# DB10025_Toplevel.net
KiCad netlist of a schematic drawn in Altium Designer
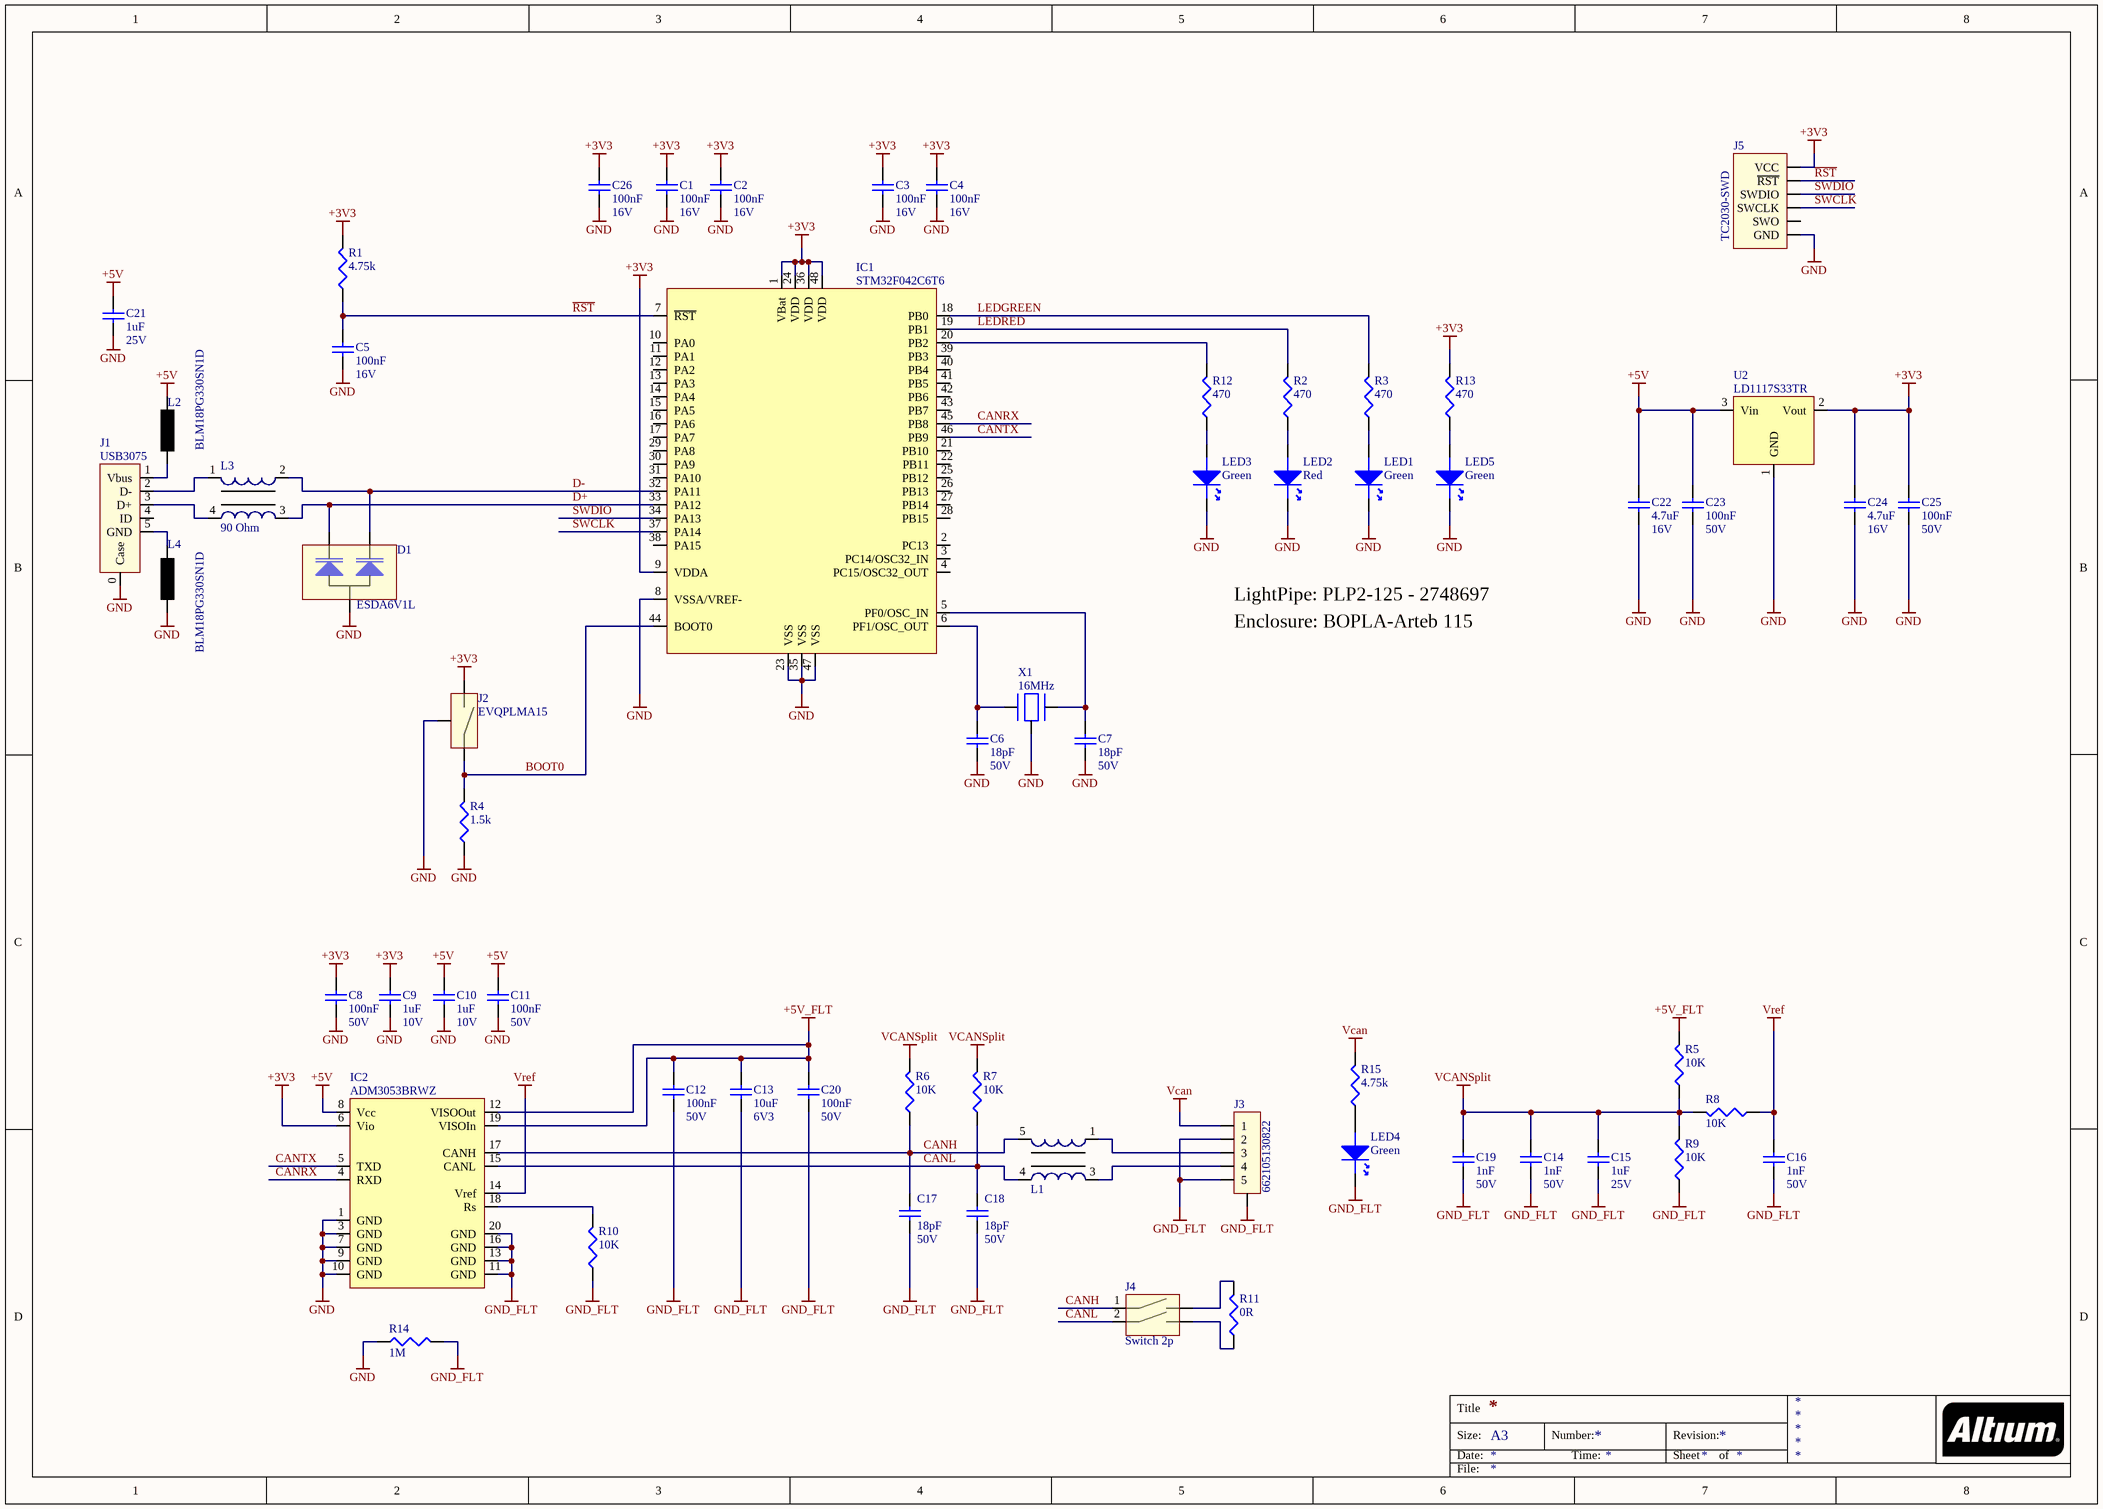
[diagram p0: DB10025_Toplevel.SchDoc]

(export (version "E")
  (design (tool "Eeschema 10.0.6"))
  (components
    (comp (ref "C1")
      (value "100nF")
      (footprint "C0402")
      (description "Capacitor, 100nF, 16V, X7R")
      (fields (field (name "VOLTAGE RATING") "16V"))
      (libsource (lib "AR_Capacitors_Ceramic") (part "100nF/0402/CER/16V"))
    )
    (comp (ref "C2")
      (value "100nF")
      (footprint "C0402")
      (description "Capacitor, 100nF, 16V, X7R")
      (fields (field (name "VOLTAGE RATING") "16V"))
      (libsource (lib "AR_Capacitors_Ceramic") (part "100nF/0402/CER/16V"))
    )
    (comp (ref "C3")
      (value "100nF")
      (footprint "C0402")
      (description "Capacitor, 100nF, 16V, X7R")
      (fields (field (name "VOLTAGE RATING") "16V"))
      (libsource (lib "AR_Capacitors_Ceramic") (part "100nF/0402/CER/16V"))
    )
    (comp (ref "C4")
      (value "100nF")
      (footprint "C0402")
      (description "Capacitor, 100nF, 16V, X7R")
      (fields (field (name "VOLTAGE RATING") "16V"))
      (libsource (lib "AR_Capacitors_Ceramic") (part "100nF/0402/CER/16V"))
    )
    (comp (ref "C5")
      (value "100nF")
      (footprint "C0402")
      (description "Capacitor, 100nF, 16V, X7R")
      (fields (field (name "VOLTAGE RATING") "16V"))
      (libsource (lib "AR_Capacitors_Ceramic") (part "100nF/0402/CER/16V"))
    )
    (comp (ref "C6")
      (value "18pF")
      (footprint "C0402")
      (description "Capacitor, 18pF, 50V, NP0")
      (fields (field (name "VOLTAGE RATING") "50V"))
      (libsource (lib "AR_Capacitors_Ceramic") (part "18pF/0402/CER/50V"))
    )
    (comp (ref "C7")
      (value "18pF")
      (footprint "C0402")
      (description "Capacitor, 18pF, 50V, NP0")
      (fields (field (name "VOLTAGE RATING") "50V"))
      (libsource (lib "AR_Capacitors_Ceramic") (part "18pF/0402/CER/50V"))
    )
    (comp (ref "C8")
      (value "100nF")
      (footprint "C0603")
      (description "Capacitor, 100nF, 50V, X7R")
      (fields (field (name "VOLTAGE RATING") "50V"))
      (libsource (lib "AR_Capacitors_Ceramic") (part "100nF/0603/CER/50V"))
    )
    (comp (ref "C9")
      (value "1uF")
      (footprint "C0603")
      (description "Capacitor, 1uF, 10V, X5R")
      (fields (field (name "VOLTAGE RATING") "10V"))
      (libsource (lib "AR_Capacitors_Ceramic") (part "1uF/0603/CER/10V/X5R"))
    )
    (comp (ref "C10")
      (value "1uF")
      (footprint "C0603")
      (description "Capacitor, 1uF, 10V, X5R")
      (fields (field (name "VOLTAGE RATING") "10V"))
      (libsource (lib "AR_Capacitors_Ceramic") (part "1uF/0603/CER/10V/X5R"))
    )
    (comp (ref "C11")
      (value "100nF")
      (footprint "C0603")
      (description "Capacitor, 100nF, 50V, X7R")
      (fields (field (name "VOLTAGE RATING") "50V"))
      (libsource (lib "AR_Capacitors_Ceramic") (part "100nF/0603/CER/50V"))
    )
    (comp (ref "C12")
      (value "100nF")
      (footprint "C0603")
      (description "Capacitor, 100nF, 50V, X7R")
      (fields (field (name "VOLTAGE RATING") "50V"))
      (libsource (lib "AR_Capacitors_Ceramic") (part "100nF/0603/CER/50V"))
    )
    (comp (ref "C13")
      (value "10uF")
      (footprint "C0603")
      (description "Capacitor, 10uF, 6.3V, X5R")
      (fields (field (name "VOLTAGE RATING") "6V3"))
      (libsource (lib "AR_Capacitors_Ceramic") (part "10uF/0603/CER/6V3/X5R"))
    )
    (comp (ref "C14")
      (value "1nF")
      (footprint "C0603")
      (description "Capacitor, 1nF, 50V, X7R")
      (fields (field (name "VOLTAGE RATING") "50V"))
      (libsource (lib "AR_Capacitors_Ceramic") (part "1nF/0603/CER/50V"))
    )
    (comp (ref "C15")
      (value "1uF")
      (footprint "C0603")
      (description "Capacitor, 1uF, 25V, X7R")
      (fields (field (name "VOLTAGE RATING") "25V"))
      (libsource (lib "AR_Capacitors_Ceramic") (part "1uF/0603/CER/25V"))
    )
    (comp (ref "C16")
      (value "1nF")
      (footprint "C0603")
      (description "Capacitor, 1nF, 50V, X7R")
      (fields (field (name "VOLTAGE RATING") "50V"))
      (libsource (lib "AR_Capacitors_Ceramic") (part "1nF/0603/CER/50V"))
    )
    (comp (ref "C17")
      (value "18pF")
      (footprint "C0603")
      (description "Capacitor, 18pF, 50V, C0G / NP0")
      (fields (field (name "VOLTAGE RATING") "50V"))
      (libsource (lib "AR_Capacitors_Ceramic") (part "18pF/0603/CER/50V"))
    )
    (comp (ref "C18")
      (value "18pF")
      (footprint "C0603")
      (description "Capacitor, 18pF, 50V, C0G / NP0")
      (fields (field (name "VOLTAGE RATING") "50V"))
      (libsource (lib "AR_Capacitors_Ceramic") (part "18pF/0603/CER/50V"))
    )
    (comp (ref "C19")
      (value "1nF")
      (footprint "C0603")
      (description "Capacitor, 1nF, 50V, X7R")
      (fields (field (name "VOLTAGE RATING") "50V"))
      (libsource (lib "AR_Capacitors_Ceramic") (part "1nF/0603/CER/50V"))
    )
    (comp (ref "C20")
      (value "100nF")
      (footprint "C0603")
      (description "Capacitor, 100nF, 50V, X7R")
      (fields (field (name "VOLTAGE RATING") "50V"))
      (libsource (lib "AR_Capacitors_Ceramic") (part "100nF/0603/CER/50V"))
    )
    (comp (ref "C21")
      (value "1uF")
      (footprint "C0603")
      (description "Capacitor, 1uF, 25V, X7R")
      (fields (field (name "VOLTAGE RATING") "25V"))
      (libsource (lib "AR_Capacitors_Ceramic") (part "1uF/0603/CER/25V"))
    )
    (comp (ref "C22")
      (value "4.7uF")
      (footprint "C-0805")
      (description "Capacitor, 4.7uF, 16V, X7R")
      (fields (field (name "VOLTAGE RATING") "16V"))
      (libsource (lib "AR_Capacitors_Ceramic") (part "4.7uF/0805/CER/16V"))
    )
    (comp (ref "C23")
      (value "100nF")
      (footprint "C-0805")
      (description "Capacitor, 100nF, 50V,  X7R")
      (fields (field (name "VOLTAGE RATING") "50V"))
      (libsource (lib "AR_Capacitors_Ceramic") (part "100nF/0805/CER/50V"))
    )
    (comp (ref "C24")
      (value "4.7uF")
      (footprint "C-0805")
      (description "Capacitor, 4.7uF, 16V, X7R")
      (fields (field (name "VOLTAGE RATING") "16V"))
      (libsource (lib "AR_Capacitors_Ceramic") (part "4.7uF/0805/CER/16V"))
    )
    (comp (ref "C25")
      (value "100nF")
      (footprint "C-0805")
      (description "Capacitor, 100nF, 50V,  X7R")
      (fields (field (name "VOLTAGE RATING") "50V"))
      (libsource (lib "AR_Capacitors_Ceramic") (part "100nF/0805/CER/50V"))
    )
    (comp (ref "C26")
      (value "100nF")
      (footprint "C0402")
      (description "Capacitor, 100nF, 16V, X7R")
      (fields (field (name "VOLTAGE RATING") "16V"))
      (libsource (lib "AR_Capacitors_Ceramic") (part "100nF/0402/CER/16V"))
    )
    (comp (ref "D1")
      (value "ESDA6V1L")
      (footprint "SOT23")
      (description "Diode TVS Dual, Vrwm: 5.25V, Vbr: 7.2V, Vc: 12.45V, Ippm: 15A")
      (libsource (lib "AR_Diodes") (part "ESDA6V1L"))
    )
    (comp (ref "IC1")
      (value "STM32F042C6T6")
      (footprint "LQFP48")
      (description "MCU, 32BIT CORTEX-M3, 72MHz")
      (libsource (lib "AR_Microcontrollers") (part "STM32F042C6T6"))
    )
    (comp (ref "IC2")
      (value "ADM3053BRWZ")
      (footprint "SOIC20")
      (description "CAN Transceiver isolated")
      (libsource (lib "AR_ICs") (part "ADM3053BRWZ"))
    )
    (comp (ref "J1")
      (value "USB3075")
      (footprint "USB3075")
      (description "USB 2.0 MICRO B, RCPT, 5POS, SMT")
      (libsource (lib "AR_Connectors") (part "USB3075"))
    )
    (comp (ref "J2")
      (value "EVQPLMA15")
      (footprint "EVQPLM")
      (description "SWITCH, TACT, 4.9MM, SMD, 2.6N")
      (libsource (lib "AR_Misc") (part "EVQPLMA15"))
    )
    (comp (ref "J3")
      (value "662105130822")
      (footprint "662105130822")
      (description "WR-MPC3 Series, 5Pin, Right Angle")
      (libsource (lib "AR_Connectors") (part "662105130822"))
    )
    (comp (ref "J4")
      (value "Switch 2p")
      (footprint "MCEMR-02")
      (description "SWITCH, DIL, SMD, 2WAY, SPST")
      (libsource (lib "AR_Misc") (part "WE-418121160802"))
    )
    (comp (ref "J5")
      (value "TC2030-SWD")
      (footprint "TC2030-IDC-NL")
      (description "TagConnect 2030")
      (libsource (lib "AR_Connectors") (part "TC2030-SWD"))
    )
    (comp (ref "L1")
      (value "CAN filter")
      (footprint "WE-SL1")
      (description "Common mode CAN filter")
      (libsource (lib "AR_Misc") (part "744212510"))
    )
    (comp (ref "L2")
      (value "BLM18PG330SN1D")
      (footprint "L0603")
      (description "Ferrite Bead, Impedance:33ohm, DC Resistance Max:0.025ohm, DC Current Rating:3A")
      (libsource (lib "AR_Inductors") (part "BLM18PG330SN1D"))
    )
    (comp (ref "L3")
      (value "90 Ohm")
      (footprint "WE-CNSW, 1206")
      (description "SMD Common Mode Noise Suppressor WE-CNSW,  Z= 90 Ohm")
      (fields
        (field (name "PARTNO") "744232090")
        (field (name "MANUFACTURER") "Würth Elektronik eiSos GmbH")
        (field (name "CREATED BY") "Christin Zierenner")
      )
      (libsource (lib "AR_Misc") (part "WE-CNSW 1206, 744232090"))
    )
    (comp (ref "L4")
      (value "BLM18PG330SN1D")
      (footprint "L0603")
      (description "Ferrite Bead, Impedance:33ohm, DC Resistance Max:0.025ohm, DC Current Rating:3A")
      (libsource (lib "AR_Inductors") (part "BLM18PG330SN1D"))
    )
    (comp (ref "LED1")
      (value "Green")
      (footprint "WL-SMSW_1204")
      (description "1204 LED Green Side")
      (libsource (lib "AR_LEDs") (part "155124GS73200"))
    )
    (comp (ref "LED2")
      (value "Red")
      (footprint "WL-SMSW_1204")
      (description "1204 LED Red Side")
      (libsource (lib "AR_LEDs") (part "155124RS73200"))
    )
    (comp (ref "LED3")
      (value "Green")
      (footprint "D-0805")
      (description "Led, Yellowish Green, Li:16mcd, Vf:2.2V, If:0.025A")
      (libsource (lib "AR_Misc") (part "SML-210MTT86N"))
    )
    (comp (ref "LED4")
      (value "Green")
      (footprint "WL-SMSW_1204")
      (description "1204 LED Green Side")
      (libsource (lib "AR_LEDs") (part "155124GS73200"))
    )
    (comp (ref "LED5")
      (value "Green")
      (footprint "D-0805")
      (description "Led, Yellowish Green, Li:16mcd, Vf:2.2V, If:0.025A")
      (libsource (lib "AR_Misc") (part "SML-210MTT86N"))
    )
    (comp (ref "R1")
      (value "4.75k")
      (footprint "0402")
      (description "Resistor, 4.75k, 0.1%, 0.0625W, 50V, 100PPM, 0402")
      (libsource (lib "AR_Resistors_SMD") (part "4.75k/0402/0063W/50V"))
    )
    (comp (ref "R2")
      (value "470")
      (footprint "0402")
      (description "Resistor, 470, 1%, 0.0625W, 50V, 100PPM, 0402")
      (libsource (lib "AR_Resistors_SMD") (part "470/0402/0063W/50V"))
    )
    (comp (ref "R3")
      (value "470")
      (footprint "0402")
      (description "Resistor, 470, 1%, 0.0625W, 50V, 100PPM, 0402")
      (libsource (lib "AR_Resistors_SMD") (part "470/0402/0063W/50V"))
    )
    (comp (ref "R4")
      (value "1.5k")
      (footprint "0402")
      (description "Resistor, 1.5k, 0.1%, 0.0625W, 50V, 100PPM, 0402")
      (libsource (lib "AR_Resistors_SMD") (part "1.5k/0402/0063W/50V"))
    )
    (comp (ref "R5")
      (value "10K")
      (footprint "0603")
      (description "Resistor, 10K, 1%, 0.063W, 50V, 100PPM, 0603")
      (libsource (lib "AR_Resistors_SMD") (part "10K/0603/0063W/50V"))
    )
    (comp (ref "R6")
      (value "10K")
      (footprint "0603")
      (description "Resistor, 10K, 1%, 0.063W, 50V, 100PPM, 0603")
      (libsource (lib "AR_Resistors_SMD") (part "10K/0603/0063W/50V"))
    )
    (comp (ref "R7")
      (value "10K")
      (footprint "0603")
      (description "Resistor, 10K, 1%, 0.063W, 50V, 100PPM, 0603")
      (libsource (lib "AR_Resistors_SMD") (part "10K/0603/0063W/50V"))
    )
    (comp (ref "R8")
      (value "10K")
      (footprint "0603")
      (description "Resistor, 10K, 1%, 0.063W, 50V, 100PPM, 0603")
      (libsource (lib "AR_Resistors_SMD") (part "10K/0603/0063W/50V"))
    )
    (comp (ref "R9")
      (value "10K")
      (footprint "0603")
      (description "Resistor, 10K, 1%, 0.063W, 50V, 100PPM, 0603")
      (libsource (lib "AR_Resistors_SMD") (part "10K/0603/0063W/50V"))
    )
    (comp (ref "R10")
      (value "10K")
      (footprint "0603")
      (description "Resistor, 10K, 1%, 0.063W, 50V, 100PPM, 0603")
      (libsource (lib "AR_Resistors_SMD") (part "10K/0603/0063W/50V"))
    )
    (comp (ref "R11")
      (value "0R")
      (footprint "0805")
      (description "Resistor, 0R, 0.1%, 0.1W, 150V, 200PPM, 0805")
      (libsource (lib "AR_Resistors_SMD") (part "0/0805/0100W/150V"))
    )
    (comp (ref "R12")
      (value "470")
      (footprint "0402")
      (description "Resistor, 470, 1%, 0.0625W, 50V, 100PPM, 0402")
      (libsource (lib "AR_Resistors_SMD") (part "470/0402/0063W/50V"))
    )
    (comp (ref "R13")
      (value "470")
      (footprint "0402")
      (description "Resistor, 470, 1%, 0.0625W, 50V, 100PPM, 0402")
      (libsource (lib "AR_Resistors_SMD") (part "470/0402/0063W/50V"))
    )
    (comp (ref "R14")
      (value "1M")
      (footprint "1206")
      (description "Resistor, 1M, 1%, 0.25W, 1kV, 200PPM, 1206")
      (libsource (lib "AR_Resistors_SMD") (part "1M/1206/0300W/1kV"))
    )
    (comp (ref "R15")
      (value "4.75k")
      (footprint "0402")
      (description "Resistor, 4.75k, 0.1%, 0.0625W, 50V, 100PPM, 0402")
      (libsource (lib "AR_Resistors_SMD") (part "4.75k/0402/0063W/50V"))
    )
    (comp (ref "U2")
      (value "LD1117S33TR")
      (footprint "SOT223")
      (description "LD1117S33TR - 3.3V LDO, REG, 0.8A, SOT223")
      (libsource (lib "AR_Vreg") (part "LD1117S33TR"))
    )
    (comp (ref "X1")
      (value "16MHz")
      (footprint "7M")
      (description "CRYSTAL, 16MHz,18PF CL, 3.2X2.5MM SMT")
      (libsource (lib "AR_Crystals") (part "7M-16.000MAAJ-T"))
    )
  )
  (nets
    (net (code "1") (name "+3V3") (class "Default")
      (node (ref "C1") (pin "2") (pinfunction "2_2") (pintype "passive"))
      (node (ref "C2") (pin "2") (pinfunction "2_2") (pintype "passive"))
      (node (ref "C24") (pin "2") (pinfunction "2_2") (pintype "passive"))
      (node (ref "C25") (pin "2") (pinfunction "2_2") (pintype "passive"))
      (node (ref "C26") (pin "2") (pinfunction "2_2") (pintype "passive"))
      (node (ref "C3") (pin "2") (pinfunction "2_2") (pintype "passive"))
      (node (ref "C4") (pin "2") (pinfunction "2_2") (pintype "passive"))
      (node (ref "C8") (pin "2") (pinfunction "2_2") (pintype "passive"))
      (node (ref "C9") (pin "2") (pinfunction "2_2") (pintype "passive"))
      (node (ref "IC1") (pin "1") (pinfunction "VBat_1") (pintype "passive"))
      (node (ref "IC1") (pin "24") (pinfunction "VDD_24") (pintype "passive"))
      (node (ref "IC1") (pin "36") (pinfunction "VDD_36") (pintype "passive"))
      (node (ref "IC1") (pin "48") (pinfunction "VDD_48") (pintype "passive"))
      (node (ref "IC1") (pin "9") (pinfunction "VDDA_9") (pintype "passive"))
      (node (ref "IC2") (pin "6") (pinfunction "Vio_6") (pintype "passive"))
      (node (ref "J2") (pin "2") (pinfunction "2_2") (pintype "passive"))
      (node (ref "J5") (pin "1") (pinfunction "VCC_1") (pintype "passive"))
      (node (ref "R1") (pin "2") (pinfunction "2_2") (pintype "passive"))
      (node (ref "R13") (pin "2") (pinfunction "2_2") (pintype "passive"))
      (node (ref "U2") (pin "2") (pinfunction "Vout_2") (pintype "passive"))
    )
    (net (code "2") (name "+5V") (class "Default")
      (node (ref "C10") (pin "2") (pinfunction "2_2") (pintype "passive"))
      (node (ref "C11") (pin "2") (pinfunction "2_2") (pintype "passive"))
      (node (ref "C21") (pin "2") (pinfunction "2_2") (pintype "passive"))
      (node (ref "C22") (pin "2") (pinfunction "2_2") (pintype "passive"))
      (node (ref "C23") (pin "2") (pinfunction "2_2") (pintype "passive"))
      (node (ref "IC2") (pin "8") (pinfunction "Vcc_8") (pintype "passive"))
      (node (ref "L2") (pin "2") (pinfunction "2_2") (pintype "passive"))
      (node (ref "U2") (pin "3") (pinfunction "Vin_3") (pintype "passive"))
    )
    (net (code "3") (name "+5V_FLT") (class "Default")
      (node (ref "C12") (pin "2") (pinfunction "2_2") (pintype "passive"))
      (node (ref "C13") (pin "2") (pinfunction "2_2") (pintype "passive"))
      (node (ref "C20") (pin "2") (pinfunction "2_2") (pintype "passive"))
      (node (ref "IC2") (pin "12") (pinfunction "VISOOut_12") (pintype "passive"))
      (node (ref "IC2") (pin "19") (pinfunction "VISOIn_19") (pintype "passive"))
      (node (ref "R5") (pin "2") (pinfunction "2_2") (pintype "passive"))
    )
    (net (code "4") (name "/BOOT0") (class "Default")
      (node (ref "IC1") (pin "44") (pinfunction "BOOT0_44") (pintype "passive"))
      (node (ref "J2") (pin "1") (pinfunction "1_1") (pintype "passive"))
      (node (ref "R4") (pin "2") (pinfunction "2_2") (pintype "passive"))
    )
    (net (code "5") (name "/CANH") (class "Default")
      (node (ref "C17") (pin "2") (pinfunction "2_2") (pintype "passive"))
      (node (ref "IC2") (pin "17") (pinfunction "CANH_17") (pintype "passive"))
      (node (ref "J4") (pin "1") (pinfunction "1_1") (pintype "passive"))
      (node (ref "L1") (pin "5") (pinfunction "5_5") (pintype "passive"))
      (node (ref "R6") (pin "1") (pinfunction "1_1") (pintype "passive"))
    )
    (net (code "6") (name "/CANL") (class "Default")
      (node (ref "C18") (pin "2") (pinfunction "2_2") (pintype "passive"))
      (node (ref "IC2") (pin "15") (pinfunction "CANL_15") (pintype "passive"))
      (node (ref "J4") (pin "2") (pinfunction "2_2") (pintype "passive"))
      (node (ref "L1") (pin "4") (pinfunction "4_4") (pintype "passive"))
      (node (ref "R7") (pin "1") (pinfunction "1_1") (pintype "passive"))
    )
    (net (code "7") (name "/CANRX") (class "Default")
      (node (ref "IC1") (pin "45") (pinfunction "PB8_45") (pintype "passive"))
      (node (ref "IC2") (pin "4") (pinfunction "RXD_4") (pintype "passive"))
    )
    (net (code "8") (name "/CANTX") (class "Default")
      (node (ref "IC1") (pin "46") (pinfunction "PB9_46") (pintype "passive"))
      (node (ref "IC2") (pin "5") (pinfunction "TXD_5") (pintype "passive"))
    )
    (net (code "9") (name "/D+") (class "Default")
      (node (ref "D1") (pin "K2") (pinfunction "K2_K2") (pintype "passive"))
      (node (ref "IC1") (pin "33") (pinfunction "PA12_33") (pintype "passive"))
      (node (ref "L3") (pin "3") (pinfunction "3_3") (pintype "passive"))
    )
    (net (code "10") (name "/D-") (class "Default")
      (node (ref "D1") (pin "K1") (pinfunction "K1_K1") (pintype "passive"))
      (node (ref "IC1") (pin "32") (pinfunction "PA11_32") (pintype "passive"))
      (node (ref "L3") (pin "2") (pinfunction "2_2") (pintype "passive"))
    )
    (net (code "11") (name "/LEDGREEN") (class "Default")
      (node (ref "IC1") (pin "18") (pinfunction "PB0_18") (pintype "passive"))
      (node (ref "R3") (pin "2") (pinfunction "2_2") (pintype "passive"))
    )
    (net (code "12") (name "/LEDRED") (class "Default")
      (node (ref "IC1") (pin "19") (pinfunction "PB1_19") (pintype "passive"))
      (node (ref "R2") (pin "2") (pinfunction "2_2") (pintype "passive"))
    )
    (net (code "13") (name "/SWCLK") (class "Default")
      (node (ref "IC1") (pin "37") (pinfunction "PA14_37") (pintype "passive"))
      (node (ref "J5") (pin "4") (pinfunction "SWCLK_4") (pintype "passive"))
    )
    (net (code "14") (name "/SWDIO") (class "Default")
      (node (ref "IC1") (pin "34") (pinfunction "PA13_34") (pintype "passive"))
      (node (ref "J5") (pin "2") (pinfunction "SWDIO_2") (pintype "passive"))
    )
    (net (code "15") (name "/~{RST}") (class "Default")
      (node (ref "C5") (pin "2") (pinfunction "2_2") (pintype "passive"))
      (node (ref "IC1") (pin "7") (pinfunction "~{RST}_7") (pintype "passive"))
      (node (ref "J5") (pin "3") (pinfunction "~{RST}_3") (pintype "passive"))
      (node (ref "R1") (pin "1") (pinfunction "1_1") (pintype "passive"))
    )
    (net (code "16") (name "GND") (class "Default")
      (node (ref "C1") (pin "1") (pinfunction "1_1") (pintype "passive"))
      (node (ref "C10") (pin "1") (pinfunction "1_1") (pintype "passive"))
      (node (ref "C11") (pin "1") (pinfunction "1_1") (pintype "passive"))
      (node (ref "C2") (pin "1") (pinfunction "1_1") (pintype "passive"))
      (node (ref "C21") (pin "1") (pinfunction "1_1") (pintype "passive"))
      (node (ref "C22") (pin "1") (pinfunction "1_1") (pintype "passive"))
      (node (ref "C23") (pin "1") (pinfunction "1_1") (pintype "passive"))
      (node (ref "C24") (pin "1") (pinfunction "1_1") (pintype "passive"))
      (node (ref "C25") (pin "1") (pinfunction "1_1") (pintype "passive"))
      (node (ref "C26") (pin "1") (pinfunction "1_1") (pintype "passive"))
      (node (ref "C3") (pin "1") (pinfunction "1_1") (pintype "passive"))
      (node (ref "C4") (pin "1") (pinfunction "1_1") (pintype "passive"))
      (node (ref "C5") (pin "1") (pinfunction "1_1") (pintype "passive"))
      (node (ref "C6") (pin "1") (pinfunction "1_1") (pintype "passive"))
      (node (ref "C7") (pin "1") (pinfunction "1_1") (pintype "passive"))
      (node (ref "C8") (pin "1") (pinfunction "1_1") (pintype "passive"))
      (node (ref "C9") (pin "1") (pinfunction "1_1") (pintype "passive"))
      (node (ref "D1") (pin "A") (pinfunction "A_A") (pintype "passive"))
      (node (ref "IC1") (pin "23") (pinfunction "VSS_23") (pintype "passive"))
      (node (ref "IC1") (pin "35") (pinfunction "VSS_35") (pintype "passive"))
      (node (ref "IC1") (pin "47") (pinfunction "VSS_47") (pintype "passive"))
      (node (ref "IC1") (pin "8") (pinfunction "VSSA/VREF-_8") (pintype "passive"))
      (node (ref "IC2") (pin "1") (pinfunction "GND_1") (pintype "passive"))
      (node (ref "IC2") (pin "10") (pinfunction "GND_10") (pintype "passive"))
      (node (ref "IC2") (pin "3") (pinfunction "GND_3") (pintype "passive"))
      (node (ref "IC2") (pin "7") (pinfunction "GND_7") (pintype "passive"))
      (node (ref "IC2") (pin "9") (pinfunction "GND_9") (pintype "passive"))
      (node (ref "J1") (pin "0") (pinfunction "Case_0") (pintype "passive"))
      (node (ref "J2") (pin "0") (pinfunction "GND_0") (pintype "passive"))
      (node (ref "J5") (pin "5") (pinfunction "GND_5") (pintype "passive"))
      (node (ref "L4") (pin "1") (pinfunction "1_1") (pintype "passive"))
      (node (ref "LED1") (pin "1") (pinfunction "K_1") (pintype "passive"))
      (node (ref "LED2") (pin "1") (pinfunction "K_1") (pintype "passive"))
      (node (ref "LED3") (pin "K") (pinfunction "K_K") (pintype "passive"))
      (node (ref "LED5") (pin "K") (pinfunction "K_K") (pintype "passive"))
      (node (ref "R14") (pin "1") (pinfunction "1_1") (pintype "passive"))
      (node (ref "R4") (pin "1") (pinfunction "1_1") (pintype "passive"))
      (node (ref "U2") (pin "1") (pinfunction "GND_1") (pintype "passive"))
      (node (ref "X1") (pin "0") (pinfunction "0_0") (pintype "power_in"))
    )
    (net (code "17") (name "GND_FLT") (class "Default")
      (node (ref "C12") (pin "1") (pinfunction "1_1") (pintype "passive"))
      (node (ref "C13") (pin "1") (pinfunction "1_1") (pintype "passive"))
      (node (ref "C14") (pin "1") (pinfunction "1_1") (pintype "passive"))
      (node (ref "C15") (pin "1") (pinfunction "1_1") (pintype "passive"))
      (node (ref "C16") (pin "1") (pinfunction "1_1") (pintype "passive"))
      (node (ref "C17") (pin "1") (pinfunction "1_1") (pintype "passive"))
      (node (ref "C18") (pin "1") (pinfunction "1_1") (pintype "passive"))
      (node (ref "C19") (pin "1") (pinfunction "1_1") (pintype "passive"))
      (node (ref "C20") (pin "1") (pinfunction "1_1") (pintype "passive"))
      (node (ref "IC2") (pin "11") (pinfunction "GND_11") (pintype "passive"))
      (node (ref "IC2") (pin "13") (pinfunction "GND_13") (pintype "passive"))
      (node (ref "IC2") (pin "16") (pinfunction "GND_16") (pintype "passive"))
      (node (ref "IC2") (pin "20") (pinfunction "GND_20") (pintype "passive"))
      (node (ref "J3") (pin "0") (pinfunction "SHLD_0") (pintype "passive"))
      (node (ref "J3") (pin "2") (pinfunction "2_2") (pintype "passive"))
      (node (ref "J3") (pin "5") (pinfunction "5_5") (pintype "passive"))
      (node (ref "LED4") (pin "1") (pinfunction "K_1") (pintype "passive"))
      (node (ref "R10") (pin "1") (pinfunction "1_1") (pintype "passive"))
      (node (ref "R14") (pin "2") (pinfunction "2_2") (pintype "passive"))
      (node (ref "R9") (pin "1") (pinfunction "1_1") (pintype "passive"))
    )
    (net (code "18") (name "Net-(IC1-PB2)") (class "Default")
      (node (ref "IC1") (pin "20") (pinfunction "PB2_20") (pintype "passive"))
      (node (ref "R12") (pin "2") (pinfunction "2_2") (pintype "passive"))
    )
    (net (code "19") (name "Net-(IC1-PF0{slash}OSC_IN)") (class "Default")
      (node (ref "C7") (pin "2") (pinfunction "2_2") (pintype "passive"))
      (node (ref "IC1") (pin "5") (pinfunction "PF0/OSC_IN_5") (pintype "passive"))
      (node (ref "X1") (pin "2") (pinfunction "2_2") (pintype "passive"))
    )
    (net (code "20") (name "Net-(IC1-PF1{slash}OSC_OUT)") (class "Default")
      (node (ref "C6") (pin "2") (pinfunction "2_2") (pintype "passive"))
      (node (ref "IC1") (pin "6") (pinfunction "PF1/OSC_OUT_6") (pintype "passive"))
      (node (ref "X1") (pin "1") (pinfunction "1_1") (pintype "passive"))
    )
    (net (code "21") (name "Net-(IC2-Rs)") (class "Default")
      (node (ref "IC2") (pin "18") (pinfunction "Rs_18") (pintype "passive"))
      (node (ref "R10") (pin "2") (pinfunction "2_2") (pintype "passive"))
    )
    (net (code "22") (name "Net-(J1-D+)") (class "Default")
      (node (ref "J1") (pin "3") (pinfunction "D+_3") (pintype "passive"))
      (node (ref "L3") (pin "4") (pinfunction "4_4") (pintype "passive"))
    )
    (net (code "23") (name "Net-(J1-D-)") (class "Default")
      (node (ref "J1") (pin "2") (pinfunction "D-_2") (pintype "passive"))
      (node (ref "L3") (pin "1") (pinfunction "1_1") (pintype "passive"))
    )
    (net (code "24") (name "Net-(J1-GND)") (class "Default")
      (node (ref "J1") (pin "5") (pinfunction "GND_5") (pintype "passive"))
      (node (ref "L4") (pin "2") (pinfunction "2_2") (pintype "passive"))
    )
    (net (code "25") (name "Net-(J1-Vbus)") (class "Default")
      (node (ref "J1") (pin "1") (pinfunction "Vbus_1") (pintype "passive"))
      (node (ref "L2") (pin "1") (pinfunction "1_1") (pintype "passive"))
    )
    (net (code "26") (name "Net-(J3-Pad3)") (class "Default")
      (node (ref "J3") (pin "3") (pinfunction "3_3") (pintype "passive"))
      (node (ref "L1") (pin "1") (pinfunction "1_1") (pintype "passive"))
    )
    (net (code "27") (name "Net-(J3-Pad4)") (class "Default")
      (node (ref "J3") (pin "4") (pinfunction "4_4") (pintype "passive"))
      (node (ref "L1") (pin "3") (pinfunction "3_3") (pintype "passive"))
    )
    (net (code "28") (name "Net-(J4-Pad3)") (class "Default")
      (node (ref "J4") (pin "3") (pinfunction "3_3") (pintype "passive"))
      (node (ref "R11") (pin "1") (pinfunction "1_1") (pintype "passive"))
    )
    (net (code "29") (name "Net-(J4-Pad4)") (class "Default")
      (node (ref "J4") (pin "4") (pinfunction "4_4") (pintype "passive"))
      (node (ref "R11") (pin "2") (pinfunction "2_2") (pintype "passive"))
    )
    (net (code "30") (name "Net-(LED1-A)") (class "Default")
      (node (ref "LED1") (pin "2") (pinfunction "A_2") (pintype "passive"))
      (node (ref "R3") (pin "1") (pinfunction "1_1") (pintype "passive"))
    )
    (net (code "31") (name "Net-(LED2-A)") (class "Default")
      (node (ref "LED2") (pin "2") (pinfunction "A_2") (pintype "passive"))
      (node (ref "R2") (pin "1") (pinfunction "1_1") (pintype "passive"))
    )
    (net (code "32") (name "Net-(LED3-PadA)") (class "Default")
      (node (ref "LED3") (pin "A") (pinfunction "A_A") (pintype "passive"))
      (node (ref "R12") (pin "1") (pinfunction "1_1") (pintype "passive"))
    )
    (net (code "33") (name "Net-(LED4-A)") (class "Default")
      (node (ref "LED4") (pin "2") (pinfunction "A_2") (pintype "passive"))
      (node (ref "R15") (pin "1") (pinfunction "1_1") (pintype "passive"))
    )
    (net (code "34") (name "Net-(LED5-PadA)") (class "Default")
      (node (ref "LED5") (pin "A") (pinfunction "A_A") (pintype "passive"))
      (node (ref "R13") (pin "1") (pinfunction "1_1") (pintype "passive"))
    )
    (net (code "35") (name "VCANSplit") (class "Default")
      (node (ref "C14") (pin "2") (pinfunction "2_2") (pintype "passive"))
      (node (ref "C15") (pin "2") (pinfunction "2_2") (pintype "passive"))
      (node (ref "C19") (pin "2") (pinfunction "2_2") (pintype "passive"))
      (node (ref "R5") (pin "1") (pinfunction "1_1") (pintype "passive"))
      (node (ref "R6") (pin "2") (pinfunction "2_2") (pintype "passive"))
      (node (ref "R7") (pin "2") (pinfunction "2_2") (pintype "passive"))
      (node (ref "R8") (pin "2") (pinfunction "2_2") (pintype "passive"))
      (node (ref "R9") (pin "2") (pinfunction "2_2") (pintype "passive"))
    )
    (net (code "36") (name "Vcan") (class "Default")
      (node (ref "J3") (pin "1") (pinfunction "1_1") (pintype "passive"))
      (node (ref "R15") (pin "2") (pinfunction "2_2") (pintype "passive"))
    )
    (net (code "37") (name "Vref") (class "Default")
      (node (ref "C16") (pin "2") (pinfunction "2_2") (pintype "passive"))
      (node (ref "IC2") (pin "14") (pinfunction "Vref_14") (pintype "passive"))
      (node (ref "R8") (pin "1") (pinfunction "1_1") (pintype "passive"))
    )
    (net (code "38") (name "unconnected-(IC1-PA0-Pad10)") (class "Default")
      (node (ref "IC1") (pin "10") (pinfunction "PA0_10") (pintype "passive"))
    )
    (net (code "39") (name "unconnected-(IC1-PA1-Pad11)") (class "Default")
      (node (ref "IC1") (pin "11") (pinfunction "PA1_11") (pintype "passive"))
    )
    (net (code "40") (name "unconnected-(IC1-PA2-Pad12)") (class "Default")
      (node (ref "IC1") (pin "12") (pinfunction "PA2_12") (pintype "passive"))
    )
    (net (code "41") (name "unconnected-(IC1-PA3-Pad13)") (class "Default")
      (node (ref "IC1") (pin "13") (pinfunction "PA3_13") (pintype "passive"))
    )
    (net (code "42") (name "unconnected-(IC1-PA4-Pad14)") (class "Default")
      (node (ref "IC1") (pin "14") (pinfunction "PA4_14") (pintype "passive"))
    )
    (net (code "43") (name "unconnected-(IC1-PA5-Pad15)") (class "Default")
      (node (ref "IC1") (pin "15") (pinfunction "PA5_15") (pintype "passive"))
    )
    (net (code "44") (name "unconnected-(IC1-PA6-Pad16)") (class "Default")
      (node (ref "IC1") (pin "16") (pinfunction "PA6_16") (pintype "passive"))
    )
    (net (code "45") (name "unconnected-(IC1-PA7-Pad17)") (class "Default")
      (node (ref "IC1") (pin "17") (pinfunction "PA7_17") (pintype "passive"))
    )
    (net (code "46") (name "unconnected-(IC1-PA8-Pad29)") (class "Default")
      (node (ref "IC1") (pin "29") (pinfunction "PA8_29") (pintype "passive"))
    )
    (net (code "47") (name "unconnected-(IC1-PA9-Pad30)") (class "Default")
      (node (ref "IC1") (pin "30") (pinfunction "PA9_30") (pintype "passive"))
    )
    (net (code "48") (name "unconnected-(IC1-PA10-Pad31)") (class "Default")
      (node (ref "IC1") (pin "31") (pinfunction "PA10_31") (pintype "passive"))
    )
    (net (code "49") (name "unconnected-(IC1-PA15-Pad38)") (class "Default")
      (node (ref "IC1") (pin "38") (pinfunction "PA15_38") (pintype "passive"))
    )
    (net (code "50") (name "unconnected-(IC1-PB3-Pad39)") (class "Default")
      (node (ref "IC1") (pin "39") (pinfunction "PB3_39") (pintype "passive"))
    )
    (net (code "51") (name "unconnected-(IC1-PB4-Pad40)") (class "Default")
      (node (ref "IC1") (pin "40") (pinfunction "PB4_40") (pintype "passive"))
    )
    (net (code "52") (name "unconnected-(IC1-PB5-Pad41)") (class "Default")
      (node (ref "IC1") (pin "41") (pinfunction "PB5_41") (pintype "passive"))
    )
    (net (code "53") (name "unconnected-(IC1-PB6-Pad42)") (class "Default")
      (node (ref "IC1") (pin "42") (pinfunction "PB6_42") (pintype "passive"))
    )
    (net (code "54") (name "unconnected-(IC1-PB7-Pad43)") (class "Default")
      (node (ref "IC1") (pin "43") (pinfunction "PB7_43") (pintype "passive"))
    )
    (net (code "55") (name "unconnected-(IC1-PB10-Pad21)") (class "Default")
      (node (ref "IC1") (pin "21") (pinfunction "PB10_21") (pintype "passive"))
    )
    (net (code "56") (name "unconnected-(IC1-PB11-Pad22)") (class "Default")
      (node (ref "IC1") (pin "22") (pinfunction "PB11_22") (pintype "passive"))
    )
    (net (code "57") (name "unconnected-(IC1-PB12-Pad25)") (class "Default")
      (node (ref "IC1") (pin "25") (pinfunction "PB12_25") (pintype "passive"))
    )
    (net (code "58") (name "unconnected-(IC1-PB13-Pad26)") (class "Default")
      (node (ref "IC1") (pin "26") (pinfunction "PB13_26") (pintype "passive"))
    )
    (net (code "59") (name "unconnected-(IC1-PB14-Pad27)") (class "Default")
      (node (ref "IC1") (pin "27") (pinfunction "PB14_27") (pintype "passive"))
    )
    (net (code "60") (name "unconnected-(IC1-PB15-Pad28)") (class "Default")
      (node (ref "IC1") (pin "28") (pinfunction "PB15_28") (pintype "passive"))
    )
    (net (code "61") (name "unconnected-(IC1-PC13-Pad2)") (class "Default")
      (node (ref "IC1") (pin "2") (pinfunction "PC13_2") (pintype "passive"))
    )
    (net (code "62") (name "unconnected-(IC1-PC14{slash}OSC32_IN-Pad3)") (class "Default")
      (node (ref "IC1") (pin "3") (pinfunction "PC14/OSC32_IN_3") (pintype "passive"))
    )
    (net (code "63") (name "unconnected-(IC1-PC15{slash}OSC32_OUT-Pad4)") (class "Default")
      (node (ref "IC1") (pin "4") (pinfunction "PC15/OSC32_OUT_4") (pintype "passive"))
    )
    (net (code "64") (name "unconnected-(J1-ID-Pad4)") (class "Default")
      (node (ref "J1") (pin "4") (pinfunction "ID_4") (pintype "passive"))
    )
    (net (code "65") (name "unconnected-(J5-SWO-Pad6)") (class "Default")
      (node (ref "J5") (pin "6") (pinfunction "SWO_6") (pintype "passive"))
    )
  )
)
